# RJ45.net
KiCad netlist of a schematic drawn in Altium Designer
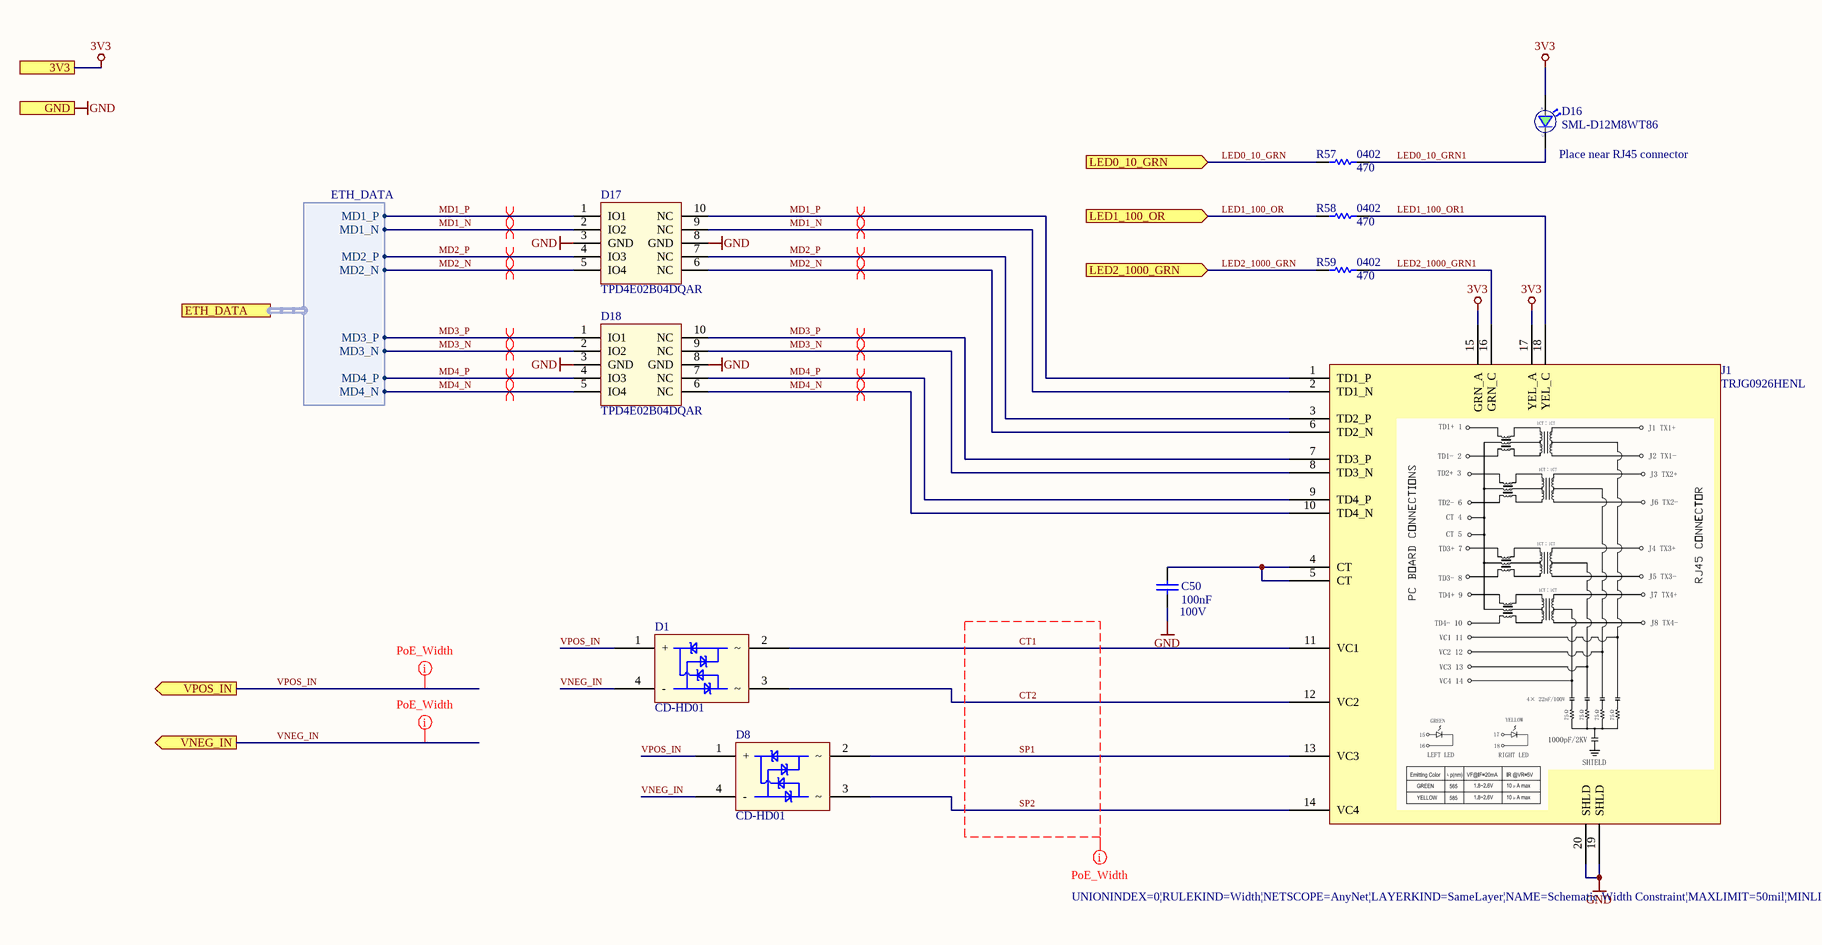
[diagram p0: RJ45.SchDoc]

(export (version "E")
  (design (tool "Eeschema 10.0.6"))
  (components
    (comp (ref "C50")
      (value "100nF")
      (footprint "CAPC0805(2012)145_N")
      (description "CAP CER 0.1UF 100V X7R 0805 10%")
      (fields
        (field (name "TOLERANCE") "10%")
        (field (name "VOLTAGE RATING") "100V")
        (field (name "Comment") "CL21B104KCFNNNE")
      )
      (libsource (lib "Luxonis LLC") (part "GRM188R61C475KAAJD"))
    )
    (comp (ref "D1")
      (value "CD-HD01")
      (footprint "CD-H01")
      (description "CD-HD0x Series Schottky Bridge Rectifier Diode 100V 4-Pin Surface Mount T/R")
      (libsource (lib "Luxonis LLC") (part "CD-HD01"))
    )
    (comp (ref "D8")
      (value "CD-HD01")
      (footprint "CD-H01")
      (description "CD-HD0x Series Schottky Bridge Rectifier Diode 100V 4-Pin Surface Mount T/R")
      (libsource (lib "Luxonis LLC") (part "CD-HD01"))
    )
    (comp (ref "D16")
      (value "SML-D12M8WT86")
      (footprint "SML_D1xx8W")
      (description "LED GREEN DIFFUSED 0603 SMD Green 572nm LED Indication - Discrete 2.2V 0603 (1608 Metric)")
      (libsource (lib "Luxonis LLC") (part "SML-D12M8WT86"))
    )
    (comp (ref "D17")
      (value "TPD4E02B04DQAR")
      (footprint "TPD4E02B04DQAR")
      (libsource (lib "Luxonis LLC") (part "TPD4E02B04DQAR"))
    )
    (comp (ref "D18")
      (value "TPD4E02B04DQAR")
      (footprint "TPD4E02B04DQAR")
      (libsource (lib "Luxonis LLC") (part "TPD4E02B04DQAR"))
    )
    (comp (ref "J1")
      (value "TRJG0926HENL")
      (footprint "TRJG0926HENL")
      (description "CONN MAGJACK 1PORT 1000 BASET")
      (libsource (lib "Luxonis LLC") (part "TRJG0926HENL"))
    )
    (comp (ref "R57")
      (value "470")
      (footprint "RESC0402(1005)_N")
      (description "RES SMD 470 OHM 1% 1/16W 0402")
      (fields
        (field (name "CASE/PACKAGE") "0402")
        (field (name "TOLERANCE") "1%")
        (field (name "Comment") "CRCW0402470RFKED")
      )
      (libsource (lib "Luxonis LLC") (part "Default resistor symbol"))
    )
    (comp (ref "R58")
      (value "470")
      (footprint "RESC0402(1005)_N")
      (description "RES SMD 470 OHM 1% 1/16W 0402")
      (fields
        (field (name "CASE/PACKAGE") "0402")
        (field (name "TOLERANCE") "1%")
        (field (name "Comment") "CRCW0402470RFKED")
      )
      (libsource (lib "Luxonis LLC") (part "Default resistor symbol"))
    )
    (comp (ref "R59")
      (value "470")
      (footprint "RESC0402(1005)_N")
      (description "RES SMD 470 OHM 1% 1/16W 0402")
      (fields
        (field (name "CASE/PACKAGE") "0402")
        (field (name "TOLERANCE") "1%")
        (field (name "Comment") "CRCW0402470RFKED")
      )
      (libsource (lib "Luxonis LLC") (part "Default resistor symbol"))
    )
  )
  (nets
    (net (code "2") (name "/CT1") (class "Default")
      (node (ref "D1") (pin "2") (pinfunction "~_2") (pintype "passive"))
      (node (ref "J1") (pin "11") (pinfunction "VC1_11") (pintype "passive"))
    )
    (net (code "3") (name "/CT2") (class "Default")
      (node (ref "D1") (pin "3") (pinfunction "~_3") (pintype "passive"))
      (node (ref "J1") (pin "12") (pinfunction "VC2_12") (pintype "passive"))
    )
    (net (code "4") (name "/LED0_10_GRN") (class "Default")
      (node (ref "R57") (pin "1") (pinfunction "1_1") (pintype "passive"))
    )
    (net (code "5") (name "/LED0_10_GRN1") (class "Default")
      (node (ref "D16") (pin "1") (pinfunction "C_1") (pintype "passive"))
      (node (ref "R57") (pin "2") (pinfunction "2_2") (pintype "passive"))
    )
    (net (code "6") (name "/LED1_100_OR") (class "Default")
      (node (ref "R58") (pin "1") (pinfunction "1_1") (pintype "passive"))
    )
    (net (code "7") (name "/LED1_100_OR1") (class "Default")
      (node (ref "J1") (pin "18") (pinfunction "YEL_C_18") (pintype "passive"))
      (node (ref "R58") (pin "2") (pinfunction "2_2") (pintype "passive"))
    )
    (net (code "8") (name "/LED2_1000_GRN") (class "Default")
      (node (ref "R59") (pin "1") (pinfunction "1_1") (pintype "passive"))
    )
    (net (code "9") (name "/LED2_1000_GRN1") (class "Default")
      (node (ref "J1") (pin "16") (pinfunction "GRN_C_16") (pintype "passive"))
      (node (ref "R59") (pin "2") (pinfunction "2_2") (pintype "passive"))
    )
    (net (code "10") (name "/MD1_N") (class "Default")
      (node (ref "D17") (pin "2") (pinfunction "IO2_2") (pintype "passive"))
      (node (ref "D17") (pin "9") (pinfunction "NC_9") (pintype "passive"))
      (node (ref "J1") (pin "2") (pinfunction "TD1_N_2") (pintype "passive"))
    )
    (net (code "11") (name "/MD1_P") (class "Default")
      (node (ref "D17") (pin "1") (pinfunction "IO1_1") (pintype "passive"))
      (node (ref "D17") (pin "10") (pinfunction "NC_10") (pintype "passive"))
      (node (ref "J1") (pin "1") (pinfunction "TD1_P_1") (pintype "passive"))
    )
    (net (code "12") (name "/MD2_N") (class "Default")
      (node (ref "D17") (pin "5") (pinfunction "IO4_5") (pintype "passive"))
      (node (ref "D17") (pin "6") (pinfunction "NC_6") (pintype "passive"))
      (node (ref "J1") (pin "6") (pinfunction "TD2_N_6") (pintype "passive"))
    )
    (net (code "13") (name "/MD2_P") (class "Default")
      (node (ref "D17") (pin "4") (pinfunction "IO3_4") (pintype "passive"))
      (node (ref "D17") (pin "7") (pinfunction "NC_7") (pintype "passive"))
      (node (ref "J1") (pin "3") (pinfunction "TD2_P_3") (pintype "passive"))
    )
    (net (code "14") (name "/MD3_N") (class "Default")
      (node (ref "D18") (pin "2") (pinfunction "IO2_2") (pintype "passive"))
      (node (ref "D18") (pin "9") (pinfunction "NC_9") (pintype "passive"))
      (node (ref "J1") (pin "8") (pinfunction "TD3_N_8") (pintype "passive"))
    )
    (net (code "15") (name "/MD3_P") (class "Default")
      (node (ref "D18") (pin "1") (pinfunction "IO1_1") (pintype "passive"))
      (node (ref "D18") (pin "10") (pinfunction "NC_10") (pintype "passive"))
      (node (ref "J1") (pin "7") (pinfunction "TD3_P_7") (pintype "passive"))
    )
    (net (code "16") (name "/MD4_N") (class "Default")
      (node (ref "D18") (pin "5") (pinfunction "IO4_5") (pintype "passive"))
      (node (ref "D18") (pin "6") (pinfunction "NC_6") (pintype "passive"))
      (node (ref "J1") (pin "10") (pinfunction "TD4_N_10") (pintype "passive"))
    )
    (net (code "17") (name "/MD4_P") (class "Default")
      (node (ref "D18") (pin "4") (pinfunction "IO3_4") (pintype "passive"))
      (node (ref "D18") (pin "7") (pinfunction "NC_7") (pintype "passive"))
      (node (ref "J1") (pin "9") (pinfunction "TD4_P_9") (pintype "passive"))
    )
    (net (code "18") (name "/SP1") (class "Default")
      (node (ref "D8") (pin "2") (pinfunction "~_2") (pintype "passive"))
      (node (ref "J1") (pin "13") (pinfunction "VC3_13") (pintype "passive"))
    )
    (net (code "19") (name "/SP2") (class "Default")
      (node (ref "D8") (pin "3") (pinfunction "~_3") (pintype "passive"))
      (node (ref "J1") (pin "14") (pinfunction "VC4_14") (pintype "passive"))
    )
    (net (code "20") (name "/VNEG_IN") (class "Default")
      (node (ref "D1") (pin "4") (pinfunction "-_4") (pintype "passive"))
      (node (ref "D8") (pin "4") (pinfunction "-_4") (pintype "passive"))
    )
    (net (code "21") (name "/VPOS_IN") (class "Default")
      (node (ref "D1") (pin "1") (pinfunction "+_1") (pintype "passive"))
      (node (ref "D8") (pin "1") (pinfunction "+_1") (pintype "passive"))
    )
    (net (code "23") (name "3V3") (class "Default")
      (node (ref "D16") (pin "2") (pinfunction "A_2") (pintype "passive"))
      (node (ref "J1") (pin "15") (pinfunction "GRN_A_15") (pintype "passive"))
      (node (ref "J1") (pin "17") (pinfunction "YEL_A_17") (pintype "passive"))
    )
    (net (code "24") (name "GND") (class "Default")
      (node (ref "C50") (pin "1") (pinfunction "1_1") (pintype "passive"))
      (node (ref "D17") (pin "3") (pinfunction "GND_3") (pintype "passive"))
      (node (ref "D17") (pin "8") (pinfunction "GND_8") (pintype "passive"))
      (node (ref "D18") (pin "3") (pinfunction "GND_3") (pintype "passive"))
      (node (ref "D18") (pin "8") (pinfunction "GND_8") (pintype "passive"))
      (node (ref "J1") (pin "19") (pinfunction "SHLD_19") (pintype "passive"))
      (node (ref "J1") (pin "20") (pinfunction "SHLD_20") (pintype "passive"))
    )
    (net (code "25") (name "Net-(C50-Pad2)") (class "Default")
      (node (ref "C50") (pin "2") (pinfunction "2_2") (pintype "passive"))
      (node (ref "J1") (pin "4") (pinfunction "CT_4") (pintype "passive"))
      (node (ref "J1") (pin "5") (pinfunction "CT_5") (pintype "passive"))
    )
  )
)
